# audio_interface.net
KiCad netlist of a schematic drawn in Altium Designer
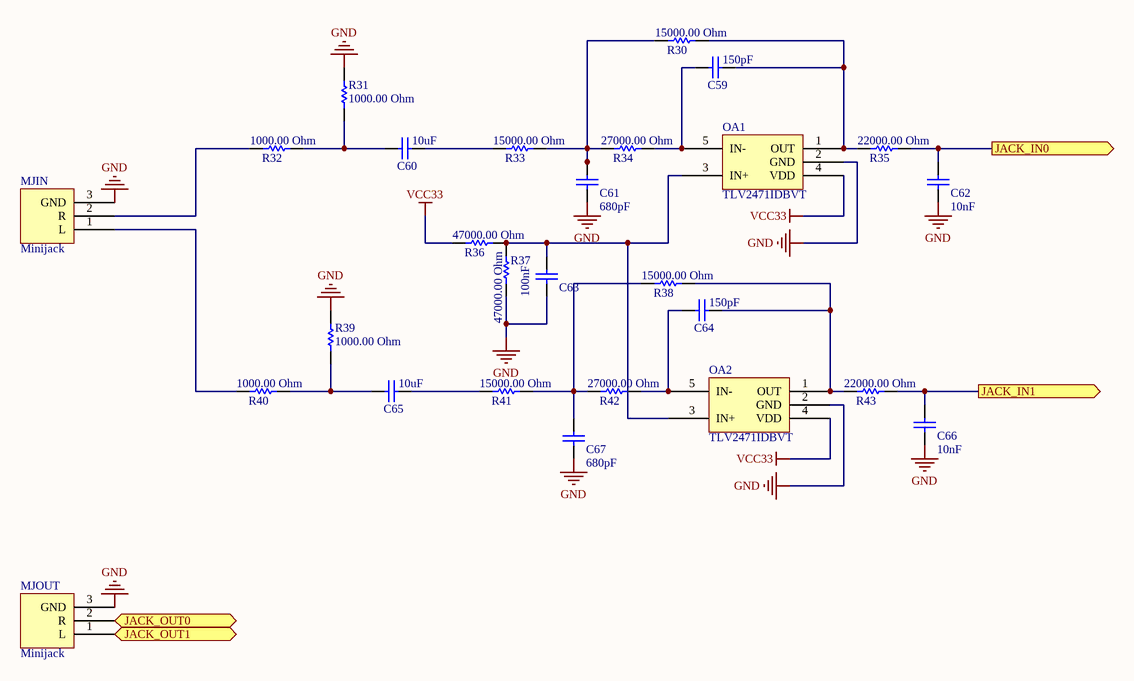
[diagram p0: audio_interface.SchDoc]

(export (version "E")
  (design (tool "Eeschema 10.0.6"))
  (components
    (comp (ref "C59")
      (value "150pF")
      (footprint "CAPC0805(2012)75_M")
      (description "CAP 150pF 100V ±1% 0805 (2012 Metric) Thickness 0.75mm SMD")
      (fields (field (name "TOLERANCE") "±1%"))
      (libsource (lib "Altium Content Vault") (part "CMP-1036-02142-1"))
    )
    (comp (ref "C60")
      (value "10uF")
      (footprint "CAPC0805(2012)145_L")
      (description "CAP 10uF 6.3V ±10% 0805 (2012 Metric) Thickness 1.45mm SMD")
      (fields (field (name "TOLERANCE") "±10%"))
      (libsource (lib "Altium Content Vault") (part "CMP-1036-04915-1"))
    )
    (comp (ref "C61")
      (value "680pF")
      (footprint "CAPC0805(2012)100_M")
      (description "CAP 680pF 6.3V ±5% 0805 (2012 Metric) Thickness 1mm SMD")
      (fields (field (name "TOLERANCE") "±5%"))
      (libsource (lib "Altium Content Vault") (part "CMP-1036-02797-1"))
    )
    (comp (ref "C62")
      (value "10nF")
      (footprint "CAPC0805(2012)100_M")
      (description "CAP 10nF 6.3V ±5% 0805 (2012 Metric) Thickness 1mm SMD")
      (fields (field (name "TOLERANCE") "±5%"))
      (libsource (lib "Altium Content Vault") (part "CMP-1036-03801-1"))
    )
    (comp (ref "C63")
      (value "100nF")
      (footprint "CAPC0805(2012)100_M")
      (description "CAP 100nF 6.3V ±5% 0805 (2012 Metric) Thickness 1mm SMD")
      (fields (field (name "TOLERANCE") "±5%"))
      (libsource (lib "Altium Content Vault") (part "CMP-1036-04390-1"))
    )
    (comp (ref "C64")
      (value "150pF")
      (footprint "CAPC0805(2012)75_M")
      (description "CAP 150pF 100V ±1% 0805 (2012 Metric) Thickness 0.75mm SMD")
      (fields (field (name "TOLERANCE") "±1%"))
      (libsource (lib "Altium Content Vault") (part "CMP-1036-02142-1"))
    )
    (comp (ref "C65")
      (value "10uF")
      (footprint "CAPC0805(2012)145_L")
      (description "CAP 10uF 6.3V ±10% 0805 (2012 Metric) Thickness 1.45mm SMD")
      (fields (field (name "TOLERANCE") "±10%"))
      (libsource (lib "Altium Content Vault") (part "CMP-1036-04915-1"))
    )
    (comp (ref "C66")
      (value "10nF")
      (footprint "CAPC0805(2012)100_M")
      (description "CAP 10nF 6.3V ±5% 0805 (2012 Metric) Thickness 1mm SMD")
      (fields (field (name "TOLERANCE") "±5%"))
      (libsource (lib "Altium Content Vault") (part "CMP-1036-03801-1"))
    )
    (comp (ref "C67")
      (value "680pF")
      (footprint "CAPC0805(2012)100_M")
      (description "CAP 680pF 6.3V ±5% 0805 (2012 Metric) Thickness 1mm SMD")
      (fields (field (name "TOLERANCE") "±5%"))
      (libsource (lib "Altium Content Vault") (part "CMP-1036-02797-1"))
    )
    (comp (ref "MJIN")
      (value "Minijack")
      (footprint "MINIJACKS")
      (libsource (lib "PowerConnector") (part "Minijack"))
    )
    (comp (ref "MJOUT")
      (value "Minijack")
      (footprint "MINIJACKS")
      (libsource (lib "PowerConnector") (part "Minijack"))
    )
    (comp (ref "OA1")
      (value "TLV2471IDBVT")
      (footprint "TLV2471IDBVT")
      (libsource (lib "PowerConnector") (part "TLV2471IDBVT"))
    )
    (comp (ref "OA2")
      (value "TLV2471IDBVT")
      (footprint "TLV2471IDBVT")
      (libsource (lib "PowerConnector") (part "TLV2471IDBVT"))
    )
    (comp (ref "R30")
      (value "15000.00 Ohm")
      (footprint "RESC0805(2012)_M")
      (description "15K 0.125W 1% 0805 (2012 Metric)  SMD")
      (fields (field (name "POWER") "0.125 W") (field (name "TOLERANCE") "1 %"))
      (libsource (lib "Altium Content Vault") (part "CMP-1013-00641-1"))
    )
    (comp (ref "R31")
      (value "1000.00 Ohm")
      (footprint "RESC0805(2012)_M")
      (description "1K 0.125W 1% 0805 (2012 Metric)  SMD")
      (fields (field (name "POWER") "0.125 W") (field (name "TOLERANCE") "1 %"))
      (libsource (lib "Altium Content Vault") (part "CMP-1013-00510-1"))
    )
    (comp (ref "R32")
      (value "1000.00 Ohm")
      (footprint "RESC0805(2012)_M")
      (description "1K 0.125W 1% 0805 (2012 Metric)  SMD")
      (fields (field (name "POWER") "0.125 W") (field (name "TOLERANCE") "1 %"))
      (libsource (lib "Altium Content Vault") (part "CMP-1013-00510-1"))
    )
    (comp (ref "R33")
      (value "15000.00 Ohm")
      (footprint "RESC0805(2012)_M")
      (description "15K 0.125W 1% 0805 (2012 Metric)  SMD")
      (fields (field (name "POWER") "0.125 W") (field (name "TOLERANCE") "1 %"))
      (libsource (lib "Altium Content Vault") (part "CMP-1013-00641-1"))
    )
    (comp (ref "R34")
      (value "27000.00 Ohm")
      (footprint "RESC0805(2012)_M")
      (description "27K 0.125W 1% 0805 (2012 Metric)  SMD")
      (fields (field (name "POWER") "0.125 W") (field (name "TOLERANCE") "1 %"))
      (libsource (lib "Altium Content Vault") (part "CMP-1013-00670-1"))
    )
    (comp (ref "R35")
      (value "22000.00 Ohm")
      (footprint "RESC0805(2012)_M")
      (description "22K 0.125W 1% 0805 (2012 Metric)  SMD")
      (fields (field (name "POWER") "0.125 W") (field (name "TOLERANCE") "1 %"))
      (libsource (lib "Altium Content Vault") (part "CMP-1013-00659-1"))
    )
    (comp (ref "R36")
      (value "47000.00 Ohm")
      (footprint "RESC0805(2012)_M")
      (description "47K 0.125W 1% 0805 (2012 Metric)  SMD")
      (fields (field (name "POWER") "0.125 W") (field (name "TOLERANCE") "1 %"))
      (libsource (lib "Altium Content Vault") (part "CMP-1013-00699-1"))
    )
    (comp (ref "R37")
      (value "47000.00 Ohm")
      (footprint "RESC0805(2012)_M")
      (description "47K 0.125W 1% 0805 (2012 Metric)  SMD")
      (fields (field (name "POWER") "0.125 W") (field (name "TOLERANCE") "1 %"))
      (libsource (lib "Altium Content Vault") (part "CMP-1013-00699-1"))
    )
    (comp (ref "R38")
      (value "15000.00 Ohm")
      (footprint "RESC0805(2012)_M")
      (description "15K 0.125W 1% 0805 (2012 Metric)  SMD")
      (fields (field (name "POWER") "0.125 W") (field (name "TOLERANCE") "1 %"))
      (libsource (lib "Altium Content Vault") (part "CMP-1013-00641-1"))
    )
    (comp (ref "R39")
      (value "1000.00 Ohm")
      (footprint "RESC0805(2012)_M")
      (description "1K 0.125W 1% 0805 (2012 Metric)  SMD")
      (fields (field (name "POWER") "0.125 W") (field (name "TOLERANCE") "1 %"))
      (libsource (lib "Altium Content Vault") (part "CMP-1013-00510-1"))
    )
    (comp (ref "R40")
      (value "1000.00 Ohm")
      (footprint "RESC0805(2012)_M")
      (description "1K 0.125W 1% 0805 (2012 Metric)  SMD")
      (fields (field (name "POWER") "0.125 W") (field (name "TOLERANCE") "1 %"))
      (libsource (lib "Altium Content Vault") (part "CMP-1013-00510-1"))
    )
    (comp (ref "R41")
      (value "15000.00 Ohm")
      (footprint "RESC0805(2012)_M")
      (description "15K 0.125W 1% 0805 (2012 Metric)  SMD")
      (fields (field (name "POWER") "0.125 W") (field (name "TOLERANCE") "1 %"))
      (libsource (lib "Altium Content Vault") (part "CMP-1013-00641-1"))
    )
    (comp (ref "R42")
      (value "27000.00 Ohm")
      (footprint "RESC0805(2012)_M")
      (description "27K 0.125W 1% 0805 (2012 Metric)  SMD")
      (fields (field (name "POWER") "0.125 W") (field (name "TOLERANCE") "1 %"))
      (libsource (lib "Altium Content Vault") (part "CMP-1013-00670-1"))
    )
    (comp (ref "R43")
      (value "22000.00 Ohm")
      (footprint "RESC0805(2012)_M")
      (description "22K 0.125W 1% 0805 (2012 Metric)  SMD")
      (fields (field (name "POWER") "0.125 W") (field (name "TOLERANCE") "1 %"))
      (libsource (lib "Altium Content Vault") (part "CMP-1013-00659-1"))
    )
  )
  (nets
    (net (code "1") (name "/JACK_IN0") (class "Default")
      (node (ref "C62") (pin "1") (pinfunction "1_1") (pintype "passive"))
      (node (ref "R35") (pin "1") (pinfunction "1_1") (pintype "passive"))
    )
    (net (code "2") (name "/JACK_IN1") (class "Default")
      (node (ref "C66") (pin "1") (pinfunction "1_1") (pintype "passive"))
      (node (ref "R43") (pin "1") (pinfunction "1_1") (pintype "passive"))
    )
    (net (code "3") (name "/JACK_OUT0") (class "Default")
      (node (ref "MJOUT") (pin "2") (pinfunction "R_2") (pintype "passive"))
    )
    (net (code "4") (name "/JACK_OUT1") (class "Default")
      (node (ref "MJOUT") (pin "1") (pinfunction "L_1") (pintype "passive"))
    )
    (net (code "5") (name "GND") (class "Default")
      (node (ref "C61") (pin "2") (pinfunction "2_2") (pintype "passive"))
      (node (ref "C62") (pin "2") (pinfunction "2_2") (pintype "passive"))
      (node (ref "C63") (pin "2") (pinfunction "2_2") (pintype "passive"))
      (node (ref "C66") (pin "2") (pinfunction "2_2") (pintype "passive"))
      (node (ref "C67") (pin "2") (pinfunction "2_2") (pintype "passive"))
      (node (ref "MJIN") (pin "3") (pinfunction "GND_3") (pintype "passive"))
      (node (ref "MJOUT") (pin "3") (pinfunction "GND_3") (pintype "passive"))
      (node (ref "OA1") (pin "2") (pinfunction "GND_2") (pintype "passive"))
      (node (ref "OA2") (pin "2") (pinfunction "GND_2") (pintype "passive"))
      (node (ref "R31") (pin "1") (pinfunction "1_1") (pintype "passive"))
      (node (ref "R37") (pin "2") (pinfunction "2_2") (pintype "passive"))
      (node (ref "R39") (pin "1") (pinfunction "1_1") (pintype "passive"))
    )
    (net (code "6") (name "Net-(C60-Pad1)") (class "Default")
      (node (ref "C60") (pin "1") (pinfunction "1_1") (pintype "passive"))
      (node (ref "R33") (pin "2") (pinfunction "2_2") (pintype "passive"))
    )
    (net (code "7") (name "Net-(C60-Pad2)") (class "Default")
      (node (ref "C60") (pin "2") (pinfunction "2_2") (pintype "passive"))
      (node (ref "R31") (pin "2") (pinfunction "2_2") (pintype "passive"))
      (node (ref "R32") (pin "1") (pinfunction "1_1") (pintype "passive"))
    )
    (net (code "8") (name "Net-(C61-Pad1)") (class "Default")
      (node (ref "C61") (pin "1") (pinfunction "1_1") (pintype "passive"))
      (node (ref "R30") (pin "2") (pinfunction "2_2") (pintype "passive"))
      (node (ref "R33") (pin "1") (pinfunction "1_1") (pintype "passive"))
      (node (ref "R34") (pin "2") (pinfunction "2_2") (pintype "passive"))
    )
    (net (code "9") (name "Net-(C65-Pad1)") (class "Default")
      (node (ref "C65") (pin "1") (pinfunction "1_1") (pintype "passive"))
      (node (ref "R41") (pin "2") (pinfunction "2_2") (pintype "passive"))
    )
    (net (code "10") (name "Net-(C65-Pad2)") (class "Default")
      (node (ref "C65") (pin "2") (pinfunction "2_2") (pintype "passive"))
      (node (ref "R39") (pin "2") (pinfunction "2_2") (pintype "passive"))
      (node (ref "R40") (pin "1") (pinfunction "1_1") (pintype "passive"))
    )
    (net (code "11") (name "Net-(C67-Pad1)") (class "Default")
      (node (ref "C67") (pin "1") (pinfunction "1_1") (pintype "passive"))
      (node (ref "R38") (pin "2") (pinfunction "2_2") (pintype "passive"))
      (node (ref "R41") (pin "1") (pinfunction "1_1") (pintype "passive"))
      (node (ref "R42") (pin "2") (pinfunction "2_2") (pintype "passive"))
    )
    (net (code "12") (name "Net-(MJIN-L)") (class "Default")
      (node (ref "MJIN") (pin "1") (pinfunction "L_1") (pintype "passive"))
      (node (ref "R40") (pin "2") (pinfunction "2_2") (pintype "passive"))
    )
    (net (code "13") (name "Net-(MJIN-R)") (class "Default")
      (node (ref "MJIN") (pin "2") (pinfunction "R_2") (pintype "passive"))
      (node (ref "R32") (pin "2") (pinfunction "2_2") (pintype "passive"))
    )
    (net (code "14") (name "Net-(OA1-IN+)") (class "Default")
      (node (ref "C63") (pin "1") (pinfunction "1_1") (pintype "passive"))
      (node (ref "OA1") (pin "3") (pinfunction "IN+_3") (pintype "passive"))
      (node (ref "OA2") (pin "3") (pinfunction "IN+_3") (pintype "passive"))
      (node (ref "R36") (pin "1") (pinfunction "1_1") (pintype "passive"))
      (node (ref "R37") (pin "1") (pinfunction "1_1") (pintype "passive"))
    )
    (net (code "15") (name "Net-(OA1-IN-)") (class "Default")
      (node (ref "C59") (pin "2") (pinfunction "2_2") (pintype "passive"))
      (node (ref "OA1") (pin "5") (pinfunction "IN-_5") (pintype "passive"))
      (node (ref "R34") (pin "1") (pinfunction "1_1") (pintype "passive"))
    )
    (net (code "16") (name "Net-(OA1-OUT)") (class "Default")
      (node (ref "C59") (pin "1") (pinfunction "1_1") (pintype "passive"))
      (node (ref "OA1") (pin "1") (pinfunction "OUT_1") (pintype "passive"))
      (node (ref "R30") (pin "1") (pinfunction "1_1") (pintype "passive"))
      (node (ref "R35") (pin "2") (pinfunction "2_2") (pintype "passive"))
    )
    (net (code "17") (name "Net-(OA2-IN-)") (class "Default")
      (node (ref "C64") (pin "2") (pinfunction "2_2") (pintype "passive"))
      (node (ref "OA2") (pin "5") (pinfunction "IN-_5") (pintype "passive"))
      (node (ref "R42") (pin "1") (pinfunction "1_1") (pintype "passive"))
    )
    (net (code "18") (name "Net-(OA2-OUT)") (class "Default")
      (node (ref "C64") (pin "1") (pinfunction "1_1") (pintype "passive"))
      (node (ref "OA2") (pin "1") (pinfunction "OUT_1") (pintype "passive"))
      (node (ref "R38") (pin "1") (pinfunction "1_1") (pintype "passive"))
      (node (ref "R43") (pin "2") (pinfunction "2_2") (pintype "passive"))
    )
    (net (code "19") (name "VCC33") (class "Default")
      (node (ref "OA1") (pin "4") (pinfunction "VDD_4") (pintype "passive"))
      (node (ref "OA2") (pin "4") (pinfunction "VDD_4") (pintype "passive"))
      (node (ref "R36") (pin "2") (pinfunction "2_2") (pintype "passive"))
    )
  )
)
